# FAD4.net
KiCad netlist of a schematic drawn in EAGLE
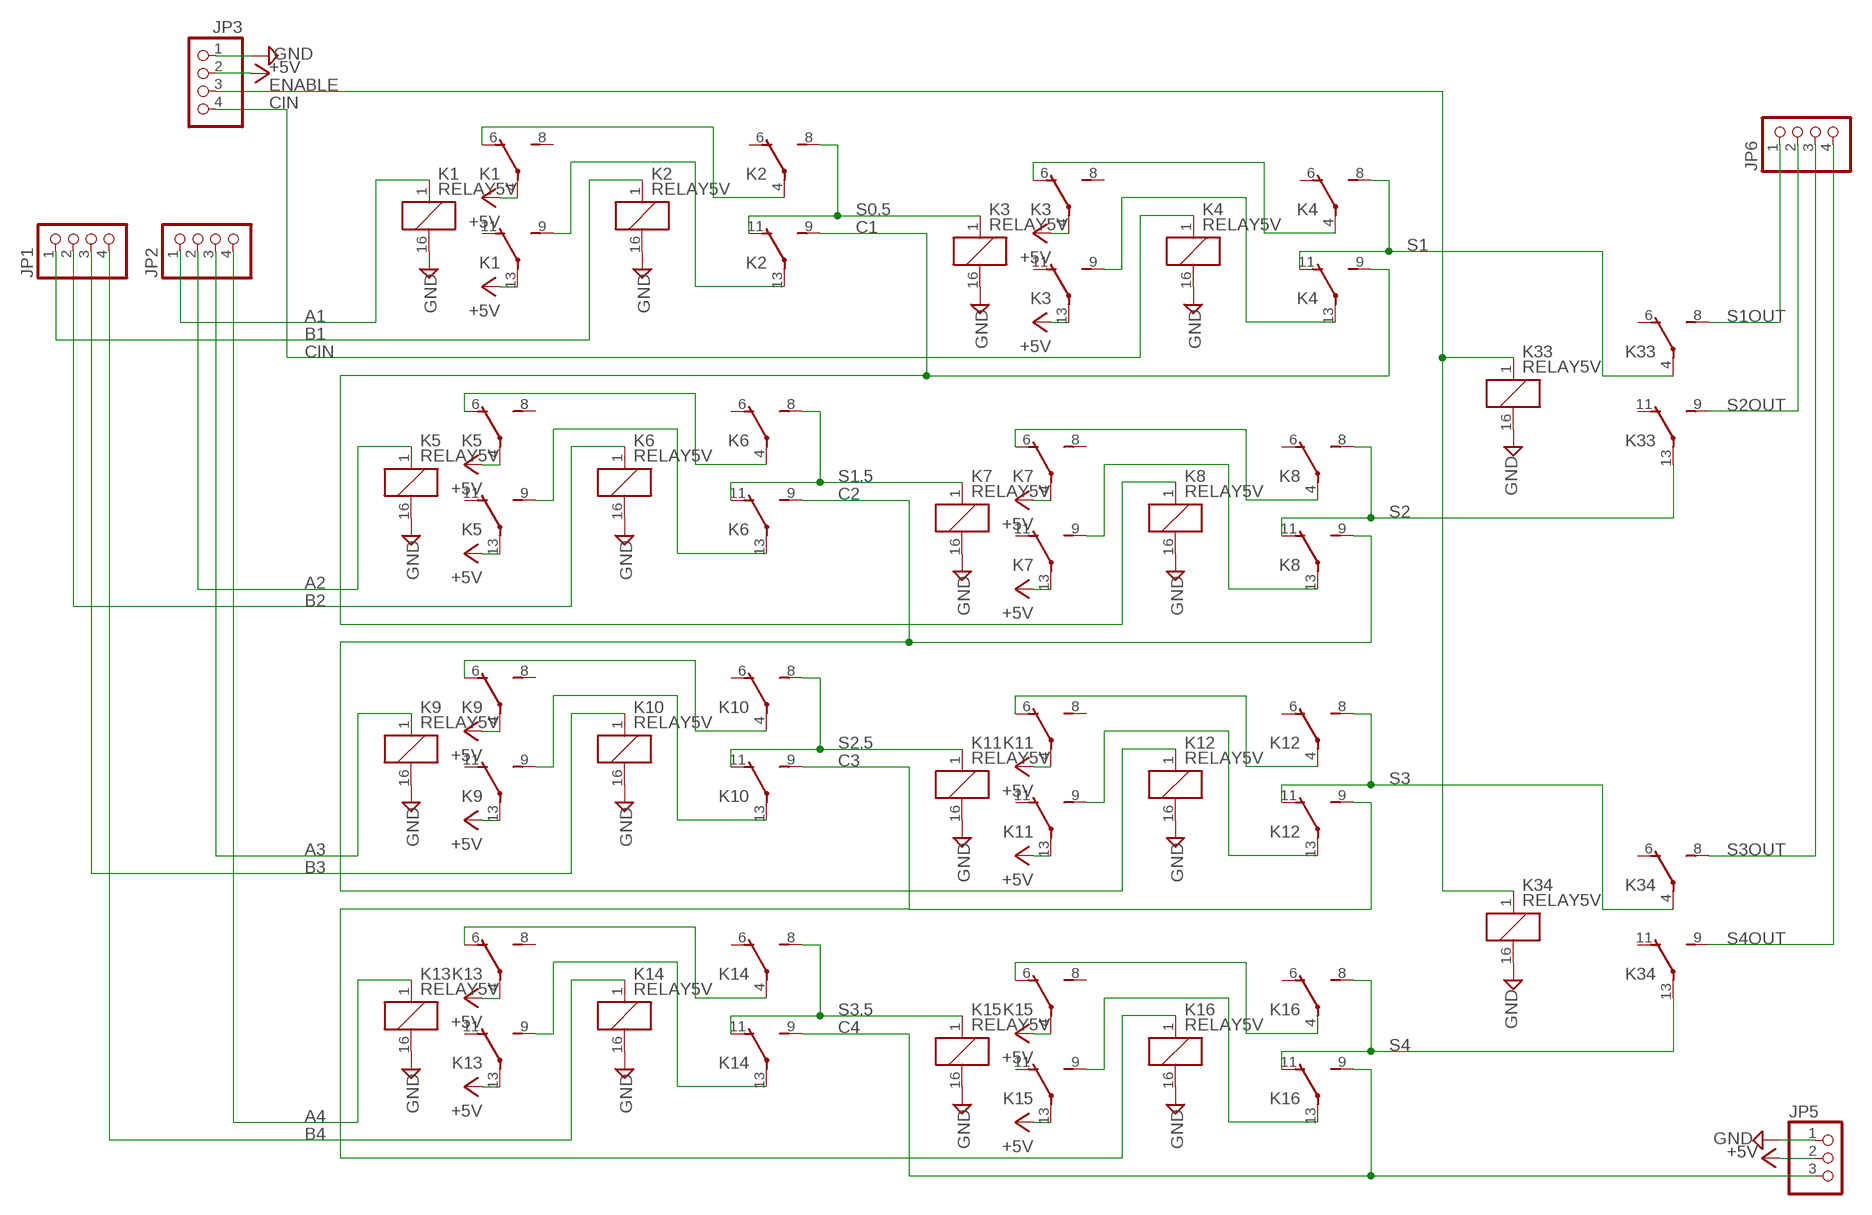
[diagram p0: schematic, sheet 1]

(export (version "E")
  (design (tool "Eeschema 10.0.6"))
  (components
    (comp (ref "JP1")
      (value "PINHD-1X4")
      (footprint "eagle-import:1X04")
      (libsource (lib "eagle-import") (part "PINHD-1X4"))
    )
    (comp (ref "JP2")
      (value "PINHD-1X4")
      (footprint "eagle-import:1X04")
      (libsource (lib "eagle-import") (part "PINHD-1X4"))
    )
    (comp (ref "JP3")
      (value "PINHD-1X4")
      (footprint "eagle-import:1X04")
      (libsource (lib "eagle-import") (part "PINHD-1X4"))
    )
    (comp (ref "JP5")
      (value "PINHD-1X3")
      (footprint "eagle-import:1X03")
      (libsource (lib "eagle-import") (part "PINHD-1X3"))
    )
    (comp (ref "JP6")
      (value "PINHD-1X4")
      (footprint "eagle-import:1X04")
      (libsource (lib "eagle-import") (part "PINHD-1X4"))
    )
    (comp (ref "K1")
      (value "RELAY5V")
      (footprint "eagle-import:DS-BT")
      (libsource (lib "eagle-import") (part "RELAY5V"))
    )
    (comp (ref "K2")
      (value "RELAY5V")
      (footprint "eagle-import:DS-BT")
      (libsource (lib "eagle-import") (part "RELAY5V"))
    )
    (comp (ref "K3")
      (value "RELAY5V")
      (footprint "eagle-import:DS-BT")
      (libsource (lib "eagle-import") (part "RELAY5V"))
    )
    (comp (ref "K4")
      (value "RELAY5V")
      (footprint "eagle-import:DS-BT")
      (libsource (lib "eagle-import") (part "RELAY5V"))
    )
    (comp (ref "K5")
      (value "RELAY5V")
      (footprint "eagle-import:DS-BT")
      (libsource (lib "eagle-import") (part "RELAY5V"))
    )
    (comp (ref "K6")
      (value "RELAY5V")
      (footprint "eagle-import:DS-BT")
      (libsource (lib "eagle-import") (part "RELAY5V"))
    )
    (comp (ref "K7")
      (value "RELAY5V")
      (footprint "eagle-import:DS-BT")
      (libsource (lib "eagle-import") (part "RELAY5V"))
    )
    (comp (ref "K8")
      (value "RELAY5V")
      (footprint "eagle-import:DS-BT")
      (libsource (lib "eagle-import") (part "RELAY5V"))
    )
    (comp (ref "K9")
      (value "RELAY5V")
      (footprint "eagle-import:DS-BT")
      (libsource (lib "eagle-import") (part "RELAY5V"))
    )
    (comp (ref "K10")
      (value "RELAY5V")
      (footprint "eagle-import:DS-BT")
      (libsource (lib "eagle-import") (part "RELAY5V"))
    )
    (comp (ref "K11")
      (value "RELAY5V")
      (footprint "eagle-import:DS-BT")
      (libsource (lib "eagle-import") (part "RELAY5V"))
    )
    (comp (ref "K12")
      (value "RELAY5V")
      (footprint "eagle-import:DS-BT")
      (libsource (lib "eagle-import") (part "RELAY5V"))
    )
    (comp (ref "K13")
      (value "RELAY5V")
      (footprint "eagle-import:DS-BT")
      (libsource (lib "eagle-import") (part "RELAY5V"))
    )
    (comp (ref "K14")
      (value "RELAY5V")
      (footprint "eagle-import:DS-BT")
      (libsource (lib "eagle-import") (part "RELAY5V"))
    )
    (comp (ref "K15")
      (value "RELAY5V")
      (footprint "eagle-import:DS-BT")
      (libsource (lib "eagle-import") (part "RELAY5V"))
    )
    (comp (ref "K16")
      (value "RELAY5V")
      (footprint "eagle-import:DS-BT")
      (libsource (lib "eagle-import") (part "RELAY5V"))
    )
    (comp (ref "K33")
      (value "RELAY5V")
      (footprint "eagle-import:DS-BT")
      (libsource (lib "eagle-import") (part "RELAY5V"))
    )
    (comp (ref "K34")
      (value "RELAY5V")
      (footprint "eagle-import:DS-BT")
      (libsource (lib "eagle-import") (part "RELAY5V"))
    )
  )
  (nets
    (net (code "1") (name "+5V") (class "Default")
      (node (ref "JP3") (pin "2") (pinfunction "2_2") (pintype "passive"))
      (node (ref "JP5") (pin "2") (pinfunction "2_2") (pintype "passive"))
      (node (ref "K1") (pin "13") (pinfunction "P_13") (pintype "passive"))
      (node (ref "K1") (pin "4") (pinfunction "P_4") (pintype "passive"))
      (node (ref "K11") (pin "13") (pinfunction "P_13") (pintype "passive"))
      (node (ref "K11") (pin "4") (pinfunction "P_4") (pintype "passive"))
      (node (ref "K13") (pin "13") (pinfunction "P_13") (pintype "passive"))
      (node (ref "K13") (pin "4") (pinfunction "P_4") (pintype "passive"))
      (node (ref "K15") (pin "13") (pinfunction "P_13") (pintype "passive"))
      (node (ref "K15") (pin "4") (pinfunction "P_4") (pintype "passive"))
      (node (ref "K3") (pin "13") (pinfunction "P_13") (pintype "passive"))
      (node (ref "K3") (pin "4") (pinfunction "P_4") (pintype "passive"))
      (node (ref "K5") (pin "13") (pinfunction "P_13") (pintype "passive"))
      (node (ref "K5") (pin "4") (pinfunction "P_4") (pintype "passive"))
      (node (ref "K7") (pin "13") (pinfunction "P_13") (pintype "passive"))
      (node (ref "K7") (pin "4") (pinfunction "P_4") (pintype "passive"))
      (node (ref "K9") (pin "13") (pinfunction "P_13") (pintype "passive"))
      (node (ref "K9") (pin "4") (pinfunction "P_4") (pintype "passive"))
    )
    (net (code "2") (name "/A1") (class "Default")
      (node (ref "JP2") (pin "1") (pinfunction "1_1") (pintype "passive"))
      (node (ref "K1") (pin "1") (pinfunction "+_1") (pintype "passive"))
    )
    (net (code "3") (name "/A2") (class "Default")
      (node (ref "JP2") (pin "2") (pinfunction "2_2") (pintype "passive"))
      (node (ref "K5") (pin "1") (pinfunction "+_1") (pintype "passive"))
    )
    (net (code "4") (name "/A3") (class "Default")
      (node (ref "JP2") (pin "3") (pinfunction "3_3") (pintype "passive"))
      (node (ref "K9") (pin "1") (pinfunction "+_1") (pintype "passive"))
    )
    (net (code "5") (name "/A4") (class "Default")
      (node (ref "JP2") (pin "4") (pinfunction "4_4") (pintype "passive"))
      (node (ref "K13") (pin "1") (pinfunction "+_1") (pintype "passive"))
    )
    (net (code "6") (name "/B1") (class "Default")
      (node (ref "JP1") (pin "1") (pinfunction "1_1") (pintype "passive"))
      (node (ref "K2") (pin "1") (pinfunction "+_1") (pintype "passive"))
    )
    (net (code "7") (name "/B2") (class "Default")
      (node (ref "JP1") (pin "2") (pinfunction "2_2") (pintype "passive"))
      (node (ref "K6") (pin "1") (pinfunction "+_1") (pintype "passive"))
    )
    (net (code "8") (name "/B3") (class "Default")
      (node (ref "JP1") (pin "3") (pinfunction "3_3") (pintype "passive"))
      (node (ref "K10") (pin "1") (pinfunction "+_1") (pintype "passive"))
    )
    (net (code "9") (name "/B4") (class "Default")
      (node (ref "JP1") (pin "4") (pinfunction "4_4") (pintype "passive"))
      (node (ref "K14") (pin "1") (pinfunction "+_1") (pintype "passive"))
    )
    (net (code "10") (name "/C1") (class "Default")
      (node (ref "K2") (pin "9") (pinfunction "S_9") (pintype "passive"))
      (node (ref "K4") (pin "9") (pinfunction "S_9") (pintype "passive"))
      (node (ref "K8") (pin "1") (pinfunction "+_1") (pintype "passive"))
    )
    (net (code "11") (name "/C2") (class "Default")
      (node (ref "K12") (pin "1") (pinfunction "+_1") (pintype "passive"))
      (node (ref "K6") (pin "9") (pinfunction "S_9") (pintype "passive"))
      (node (ref "K8") (pin "9") (pinfunction "S_9") (pintype "passive"))
    )
    (net (code "12") (name "/C3") (class "Default")
      (node (ref "K10") (pin "9") (pinfunction "S_9") (pintype "passive"))
      (node (ref "K12") (pin "9") (pinfunction "S_9") (pintype "passive"))
      (node (ref "K16") (pin "1") (pinfunction "+_1") (pintype "passive"))
    )
    (net (code "13") (name "/C4") (class "Default")
      (node (ref "JP5") (pin "3") (pinfunction "3_3") (pintype "passive"))
      (node (ref "K14") (pin "9") (pinfunction "S_9") (pintype "passive"))
      (node (ref "K16") (pin "9") (pinfunction "S_9") (pintype "passive"))
    )
    (net (code "14") (name "/CIN") (class "Default")
      (node (ref "JP3") (pin "4") (pinfunction "4_4") (pintype "passive"))
      (node (ref "K4") (pin "1") (pinfunction "+_1") (pintype "passive"))
    )
    (net (code "15") (name "/ENABLE") (class "Default")
      (node (ref "JP3") (pin "3") (pinfunction "3_3") (pintype "passive"))
      (node (ref "K33") (pin "1") (pinfunction "+_1") (pintype "passive"))
      (node (ref "K34") (pin "1") (pinfunction "+_1") (pintype "passive"))
    )
    (net (code "16") (name "/S0.5") (class "Default")
      (node (ref "K2") (pin "11") (pinfunction "O_11") (pintype "passive"))
      (node (ref "K2") (pin "8") (pinfunction "S_8") (pintype "passive"))
      (node (ref "K3") (pin "1") (pinfunction "+_1") (pintype "passive"))
    )
    (net (code "17") (name "/S1") (class "Default")
      (node (ref "K33") (pin "4") (pinfunction "P_4") (pintype "passive"))
      (node (ref "K4") (pin "11") (pinfunction "O_11") (pintype "passive"))
      (node (ref "K4") (pin "8") (pinfunction "S_8") (pintype "passive"))
    )
    (net (code "18") (name "/S1.5") (class "Default")
      (node (ref "K6") (pin "11") (pinfunction "O_11") (pintype "passive"))
      (node (ref "K6") (pin "8") (pinfunction "S_8") (pintype "passive"))
      (node (ref "K7") (pin "1") (pinfunction "+_1") (pintype "passive"))
    )
    (net (code "19") (name "/S1OUT") (class "Default")
      (node (ref "JP6") (pin "1") (pinfunction "1_1") (pintype "passive"))
      (node (ref "K33") (pin "8") (pinfunction "S_8") (pintype "passive"))
    )
    (net (code "20") (name "/S2") (class "Default")
      (node (ref "K33") (pin "13") (pinfunction "P_13") (pintype "passive"))
      (node (ref "K8") (pin "11") (pinfunction "O_11") (pintype "passive"))
      (node (ref "K8") (pin "8") (pinfunction "S_8") (pintype "passive"))
    )
    (net (code "21") (name "/S2.5") (class "Default")
      (node (ref "K10") (pin "11") (pinfunction "O_11") (pintype "passive"))
      (node (ref "K10") (pin "8") (pinfunction "S_8") (pintype "passive"))
      (node (ref "K11") (pin "1") (pinfunction "+_1") (pintype "passive"))
    )
    (net (code "22") (name "/S2OUT") (class "Default")
      (node (ref "JP6") (pin "2") (pinfunction "2_2") (pintype "passive"))
      (node (ref "K33") (pin "9") (pinfunction "S_9") (pintype "passive"))
    )
    (net (code "23") (name "/S3") (class "Default")
      (node (ref "K12") (pin "11") (pinfunction "O_11") (pintype "passive"))
      (node (ref "K12") (pin "8") (pinfunction "S_8") (pintype "passive"))
      (node (ref "K34") (pin "4") (pinfunction "P_4") (pintype "passive"))
    )
    (net (code "24") (name "/S3.5") (class "Default")
      (node (ref "K14") (pin "11") (pinfunction "O_11") (pintype "passive"))
      (node (ref "K14") (pin "8") (pinfunction "S_8") (pintype "passive"))
      (node (ref "K15") (pin "1") (pinfunction "+_1") (pintype "passive"))
    )
    (net (code "25") (name "/S3OUT") (class "Default")
      (node (ref "JP6") (pin "3") (pinfunction "3_3") (pintype "passive"))
      (node (ref "K34") (pin "8") (pinfunction "S_8") (pintype "passive"))
    )
    (net (code "26") (name "/S4") (class "Default")
      (node (ref "K16") (pin "11") (pinfunction "O_11") (pintype "passive"))
      (node (ref "K16") (pin "8") (pinfunction "S_8") (pintype "passive"))
      (node (ref "K34") (pin "13") (pinfunction "P_13") (pintype "passive"))
    )
    (net (code "27") (name "/S4OUT") (class "Default")
      (node (ref "JP6") (pin "4") (pinfunction "4_4") (pintype "passive"))
      (node (ref "K34") (pin "9") (pinfunction "S_9") (pintype "passive"))
    )
    (net (code "28") (name "GND") (class "Default")
      (node (ref "JP3") (pin "1") (pinfunction "1_1") (pintype "passive"))
      (node (ref "JP5") (pin "1") (pinfunction "1_1") (pintype "passive"))
      (node (ref "K1") (pin "16") (pinfunction "-_16") (pintype "passive"))
      (node (ref "K10") (pin "16") (pinfunction "-_16") (pintype "passive"))
      (node (ref "K11") (pin "16") (pinfunction "-_16") (pintype "passive"))
      (node (ref "K12") (pin "16") (pinfunction "-_16") (pintype "passive"))
      (node (ref "K13") (pin "16") (pinfunction "-_16") (pintype "passive"))
      (node (ref "K14") (pin "16") (pinfunction "-_16") (pintype "passive"))
      (node (ref "K15") (pin "16") (pinfunction "-_16") (pintype "passive"))
      (node (ref "K16") (pin "16") (pinfunction "-_16") (pintype "passive"))
      (node (ref "K2") (pin "16") (pinfunction "-_16") (pintype "passive"))
      (node (ref "K3") (pin "16") (pinfunction "-_16") (pintype "passive"))
      (node (ref "K33") (pin "16") (pinfunction "-_16") (pintype "passive"))
      (node (ref "K34") (pin "16") (pinfunction "-_16") (pintype "passive"))
      (node (ref "K4") (pin "16") (pinfunction "-_16") (pintype "passive"))
      (node (ref "K5") (pin "16") (pinfunction "-_16") (pintype "passive"))
      (node (ref "K6") (pin "16") (pinfunction "-_16") (pintype "passive"))
      (node (ref "K7") (pin "16") (pinfunction "-_16") (pintype "passive"))
      (node (ref "K8") (pin "16") (pinfunction "-_16") (pintype "passive"))
      (node (ref "K9") (pin "16") (pinfunction "-_16") (pintype "passive"))
    )
    (net (code "29") (name "Net-(K1B-O)") (class "Default")
      (node (ref "K1") (pin "6") (pinfunction "O_6") (pintype "passive"))
      (node (ref "K2") (pin "4") (pinfunction "P_4") (pintype "passive"))
    )
    (net (code "30") (name "Net-(K1C-S)") (class "Default")
      (node (ref "K1") (pin "9") (pinfunction "S_9") (pintype "passive"))
      (node (ref "K2") (pin "13") (pinfunction "P_13") (pintype "passive"))
    )
    (net (code "31") (name "Net-(K3B-O)") (class "Default")
      (node (ref "K3") (pin "6") (pinfunction "O_6") (pintype "passive"))
      (node (ref "K4") (pin "4") (pinfunction "P_4") (pintype "passive"))
    )
    (net (code "32") (name "Net-(K3C-S)") (class "Default")
      (node (ref "K3") (pin "9") (pinfunction "S_9") (pintype "passive"))
      (node (ref "K4") (pin "13") (pinfunction "P_13") (pintype "passive"))
    )
    (net (code "33") (name "Net-(K5B-O)") (class "Default")
      (node (ref "K5") (pin "6") (pinfunction "O_6") (pintype "passive"))
      (node (ref "K6") (pin "4") (pinfunction "P_4") (pintype "passive"))
    )
    (net (code "34") (name "Net-(K5C-S)") (class "Default")
      (node (ref "K5") (pin "9") (pinfunction "S_9") (pintype "passive"))
      (node (ref "K6") (pin "13") (pinfunction "P_13") (pintype "passive"))
    )
    (net (code "35") (name "Net-(K7B-O)") (class "Default")
      (node (ref "K7") (pin "6") (pinfunction "O_6") (pintype "passive"))
      (node (ref "K8") (pin "4") (pinfunction "P_4") (pintype "passive"))
    )
    (net (code "36") (name "Net-(K7C-S)") (class "Default")
      (node (ref "K7") (pin "9") (pinfunction "S_9") (pintype "passive"))
      (node (ref "K8") (pin "13") (pinfunction "P_13") (pintype "passive"))
    )
    (net (code "37") (name "Net-(K10B-P)") (class "Default")
      (node (ref "K10") (pin "4") (pinfunction "P_4") (pintype "passive"))
      (node (ref "K9") (pin "6") (pinfunction "O_6") (pintype "passive"))
    )
    (net (code "38") (name "Net-(K10C-P)") (class "Default")
      (node (ref "K10") (pin "13") (pinfunction "P_13") (pintype "passive"))
      (node (ref "K9") (pin "9") (pinfunction "S_9") (pintype "passive"))
    )
    (net (code "39") (name "Net-(K11B-O)") (class "Default")
      (node (ref "K11") (pin "6") (pinfunction "O_6") (pintype "passive"))
      (node (ref "K12") (pin "4") (pinfunction "P_4") (pintype "passive"))
    )
    (net (code "40") (name "Net-(K11C-S)") (class "Default")
      (node (ref "K11") (pin "9") (pinfunction "S_9") (pintype "passive"))
      (node (ref "K12") (pin "13") (pinfunction "P_13") (pintype "passive"))
    )
    (net (code "41") (name "Net-(K13B-O)") (class "Default")
      (node (ref "K13") (pin "6") (pinfunction "O_6") (pintype "passive"))
      (node (ref "K14") (pin "4") (pinfunction "P_4") (pintype "passive"))
    )
    (net (code "42") (name "Net-(K13C-S)") (class "Default")
      (node (ref "K13") (pin "9") (pinfunction "S_9") (pintype "passive"))
      (node (ref "K14") (pin "13") (pinfunction "P_13") (pintype "passive"))
    )
    (net (code "43") (name "Net-(K15B-O)") (class "Default")
      (node (ref "K15") (pin "6") (pinfunction "O_6") (pintype "passive"))
      (node (ref "K16") (pin "4") (pinfunction "P_4") (pintype "passive"))
    )
    (net (code "44") (name "Net-(K15C-S)") (class "Default")
      (node (ref "K15") (pin "9") (pinfunction "S_9") (pintype "passive"))
      (node (ref "K16") (pin "13") (pinfunction "P_13") (pintype "passive"))
    )
    (net (code "45") (name "unconnected-(K1B-S-Pad8)") (class "Default")
      (node (ref "K1") (pin "8") (pinfunction "S_8") (pintype "passive"))
    )
    (net (code "46") (name "unconnected-(K1C-O-Pad11)") (class "Default")
      (node (ref "K1") (pin "11") (pinfunction "O_11") (pintype "passive"))
    )
    (net (code "47") (name "unconnected-(K2B-O-Pad6)") (class "Default")
      (node (ref "K2") (pin "6") (pinfunction "O_6") (pintype "passive"))
    )
    (net (code "48") (name "unconnected-(K3B-S-Pad8)") (class "Default")
      (node (ref "K3") (pin "8") (pinfunction "S_8") (pintype "passive"))
    )
    (net (code "49") (name "unconnected-(K3C-O-Pad11)") (class "Default")
      (node (ref "K3") (pin "11") (pinfunction "O_11") (pintype "passive"))
    )
    (net (code "50") (name "unconnected-(K4B-O-Pad6)") (class "Default")
      (node (ref "K4") (pin "6") (pinfunction "O_6") (pintype "passive"))
    )
    (net (code "51") (name "unconnected-(K5B-S-Pad8)") (class "Default")
      (node (ref "K5") (pin "8") (pinfunction "S_8") (pintype "passive"))
    )
    (net (code "52") (name "unconnected-(K5C-O-Pad11)") (class "Default")
      (node (ref "K5") (pin "11") (pinfunction "O_11") (pintype "passive"))
    )
    (net (code "53") (name "unconnected-(K6B-O-Pad6)") (class "Default")
      (node (ref "K6") (pin "6") (pinfunction "O_6") (pintype "passive"))
    )
    (net (code "54") (name "unconnected-(K7B-S-Pad8)") (class "Default")
      (node (ref "K7") (pin "8") (pinfunction "S_8") (pintype "passive"))
    )
    (net (code "55") (name "unconnected-(K7C-O-Pad11)") (class "Default")
      (node (ref "K7") (pin "11") (pinfunction "O_11") (pintype "passive"))
    )
    (net (code "56") (name "unconnected-(K8B-O-Pad6)") (class "Default")
      (node (ref "K8") (pin "6") (pinfunction "O_6") (pintype "passive"))
    )
    (net (code "57") (name "unconnected-(K9B-S-Pad8)") (class "Default")
      (node (ref "K9") (pin "8") (pinfunction "S_8") (pintype "passive"))
    )
    (net (code "58") (name "unconnected-(K9C-O-Pad11)") (class "Default")
      (node (ref "K9") (pin "11") (pinfunction "O_11") (pintype "passive"))
    )
    (net (code "59") (name "unconnected-(K10B-O-Pad6)") (class "Default")
      (node (ref "K10") (pin "6") (pinfunction "O_6") (pintype "passive"))
    )
    (net (code "60") (name "unconnected-(K11B-S-Pad8)") (class "Default")
      (node (ref "K11") (pin "8") (pinfunction "S_8") (pintype "passive"))
    )
    (net (code "61") (name "unconnected-(K11C-O-Pad11)") (class "Default")
      (node (ref "K11") (pin "11") (pinfunction "O_11") (pintype "passive"))
    )
    (net (code "62") (name "unconnected-(K12B-O-Pad6)") (class "Default")
      (node (ref "K12") (pin "6") (pinfunction "O_6") (pintype "passive"))
    )
    (net (code "63") (name "unconnected-(K13B-S-Pad8)") (class "Default")
      (node (ref "K13") (pin "8") (pinfunction "S_8") (pintype "passive"))
    )
    (net (code "64") (name "unconnected-(K13C-O-Pad11)") (class "Default")
      (node (ref "K13") (pin "11") (pinfunction "O_11") (pintype "passive"))
    )
    (net (code "65") (name "unconnected-(K14B-O-Pad6)") (class "Default")
      (node (ref "K14") (pin "6") (pinfunction "O_6") (pintype "passive"))
    )
    (net (code "66") (name "unconnected-(K15B-S-Pad8)") (class "Default")
      (node (ref "K15") (pin "8") (pinfunction "S_8") (pintype "passive"))
    )
    (net (code "67") (name "unconnected-(K15C-O-Pad11)") (class "Default")
      (node (ref "K15") (pin "11") (pinfunction "O_11") (pintype "passive"))
    )
    (net (code "68") (name "unconnected-(K16B-O-Pad6)") (class "Default")
      (node (ref "K16") (pin "6") (pinfunction "O_6") (pintype "passive"))
    )
    (net (code "69") (name "unconnected-(K33B-O-Pad6)") (class "Default")
      (node (ref "K33") (pin "6") (pinfunction "O_6") (pintype "passive"))
    )
    (net (code "70") (name "unconnected-(K33C-O-Pad11)") (class "Default")
      (node (ref "K33") (pin "11") (pinfunction "O_11") (pintype "passive"))
    )
    (net (code "71") (name "unconnected-(K34B-O-Pad6)") (class "Default")
      (node (ref "K34") (pin "6") (pinfunction "O_6") (pintype "passive"))
    )
    (net (code "72") (name "unconnected-(K34C-O-Pad11)") (class "Default")
      (node (ref "K34") (pin "11") (pinfunction "O_11") (pintype "passive"))
    )
  )
)
